# SparkFun_TMC6300_Breakout.net
KiCad netlist of a schematic drawn in EAGLE
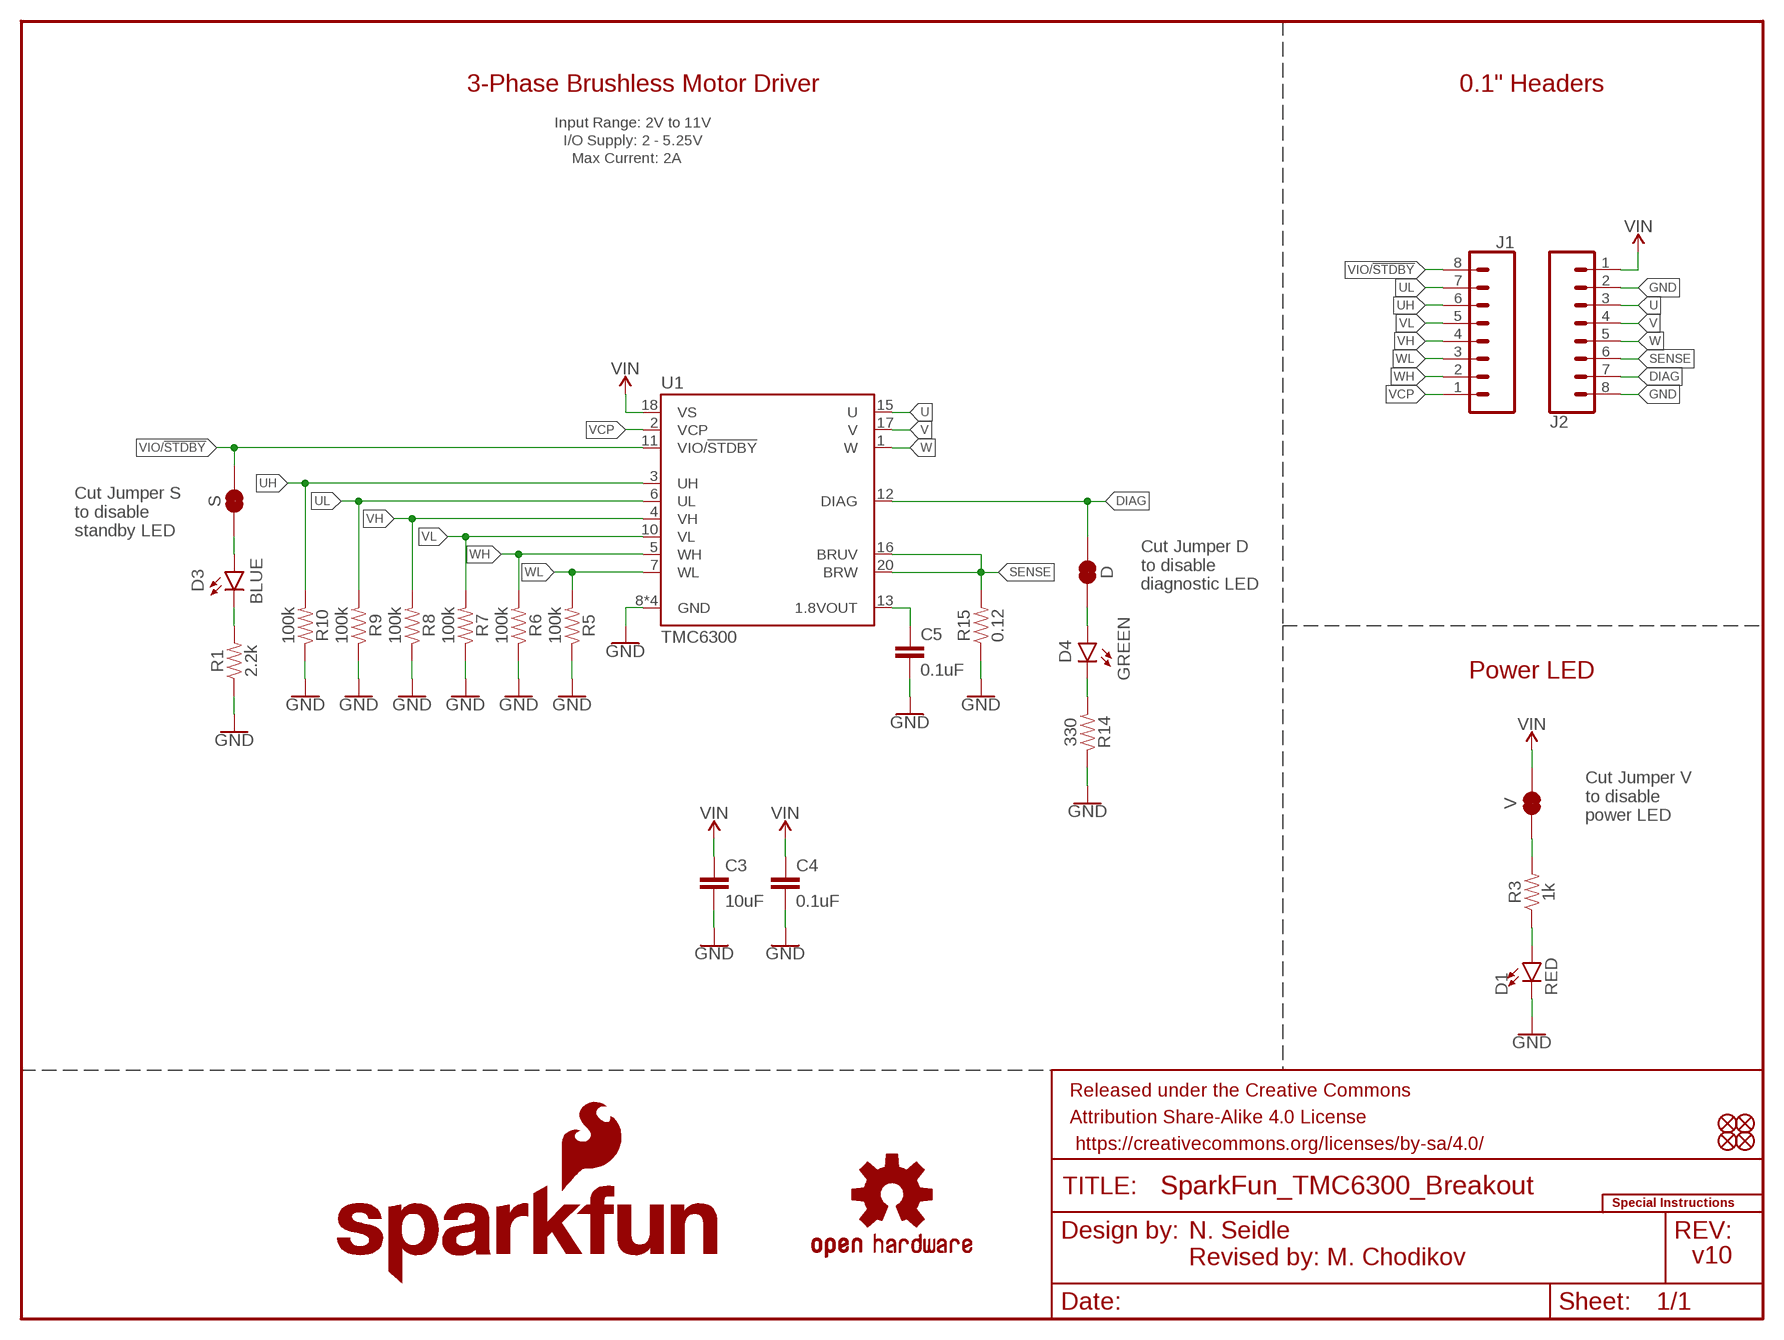
[diagram p0: schematic, sheet 1]

(export (version "E")
  (design (tool "Eeschema 10.0.6"))
  (components
    (comp (ref "C3")
      (value "10uF")
      (footprint "eagle-import:0805")
      (libsource (lib "eagle-import") (part "10UF-0805-25V-10%"))
    )
    (comp (ref "C4")
      (value "0.1uF")
      (footprint "eagle-import:0603")
      (libsource (lib "eagle-import") (part "0.1UF-0603-25V-10%-X7R-WE"))
    )
    (comp (ref "C5")
      (value "0.1uF")
      (footprint "eagle-import:0603")
      (libsource (lib "eagle-import") (part "0.1UF-0603-25V-10%-X7R-WE"))
    )
    (comp (ref "D")
      (value "JUMPER-SMT_2_NC_TRACE_SILK")
      (footprint "eagle-import:SMT-JUMPER_2_NC_TRACE_SILK")
      (libsource (lib "eagle-import") (part "JUMPER-SMT_2_NC_TRACE_SILK"))
    )
    (comp (ref "D1")
      (value "RED")
      (footprint "eagle-import:LED-0603")
      (libsource (lib "eagle-import") (part "LED-RED0603"))
    )
    (comp (ref "D3")
      (value "BLUE")
      (footprint "eagle-import:LED-0603")
      (libsource (lib "eagle-import") (part "LED-BLUE0603"))
    )
    (comp (ref "D4")
      (value "GREEN")
      (footprint "eagle-import:LED-0603")
      (libsource (lib "eagle-import") (part "LED-GREEN0603"))
    )
    (comp (ref "FD1")
      (value "FIDUCIALUFIDUCIAL")
      (footprint "eagle-import:FIDUCIAL-MICRO")
      (libsource (lib "eagle-import") (part "FIDUCIALUFIDUCIAL"))
    )
    (comp (ref "FD2")
      (value "FIDUCIALUFIDUCIAL")
      (footprint "eagle-import:FIDUCIAL-MICRO")
      (libsource (lib "eagle-import") (part "FIDUCIALUFIDUCIAL"))
    )
    (comp (ref "FD3")
      (value "FIDUCIALUFIDUCIAL")
      (footprint "eagle-import:FIDUCIAL-MICRO")
      (libsource (lib "eagle-import") (part "FIDUCIALUFIDUCIAL"))
    )
    (comp (ref "FD4")
      (value "FIDUCIALUFIDUCIAL")
      (footprint "eagle-import:FIDUCIAL-MICRO")
      (libsource (lib "eagle-import") (part "FIDUCIALUFIDUCIAL"))
    )
    (comp (ref "FRAME1")
      (value "FRAME-LETTER")
      (footprint "eagle-import:CREATIVE_COMMONS")
      (fields (field (name "DESIGNER") "Ricardo Ramos"))
      (libsource (lib "eagle-import") (part "FRAME-LETTER"))
    )
    (comp (ref "J1")
      (value "CONN_08LOCK_NO_SILK")
      (footprint "eagle-import:1X08_LOCK_NO_SILK")
      (libsource (lib "eagle-import") (part "CONN_08LOCK_NO_SILK"))
    )
    (comp (ref "J2")
      (value "CONN_08LOCK_NO_SILK")
      (footprint "eagle-import:1X08_LOCK_NO_SILK")
      (libsource (lib "eagle-import") (part "CONN_08LOCK_NO_SILK"))
    )
    (comp (ref "LOGO2")
      (value "SPECIAL_INSTRUCTIONS-ORDERING")
      (footprint "eagle-import:ORDERING_INSTRUCTIONS")
      (libsource (lib "eagle-import") (part "SPECIAL_INSTRUCTIONS-ORDERING"))
    )
    (comp (ref "LOGO3")
      (value "SFE_LOGO_NAME.08_INCH")
      (footprint "eagle-import:SFE_LOGO_NAME_.08")
      (libsource (lib "eagle-import") (part "SFE_LOGO_NAME.08_INCH"))
    )
    (comp (ref "LOGO4")
      (value "SFE_LOGO_FLAME.1_INCH")
      (footprint "eagle-import:SFE_LOGO_FLAME_.1")
      (libsource (lib "eagle-import") (part "SFE_LOGO_FLAME.1_INCH"))
    )
    (comp (ref "LOGO5")
      (value "OSHW-LOGOS")
      (footprint "eagle-import:OSHW-LOGO-S")
      (libsource (lib "eagle-import") (part "OSHW-LOGOS"))
    )
    (comp (ref "R1")
      (value "2.2k")
      (footprint "eagle-import:0603")
      (libsource (lib "eagle-import") (part "2.2KOHM-0603-1/10W-1%"))
    )
    (comp (ref "R3")
      (value "1k")
      (footprint "eagle-import:0603")
      (libsource (lib "eagle-import") (part "1KOHM-0603-1/10W-1%"))
    )
    (comp (ref "R5")
      (value "100k")
      (footprint "eagle-import:0603")
      (libsource (lib "eagle-import") (part "100KOHM-0603-1/10W-1%"))
    )
    (comp (ref "R6")
      (value "100k")
      (footprint "eagle-import:0603")
      (libsource (lib "eagle-import") (part "100KOHM-0603-1/10W-1%"))
    )
    (comp (ref "R7")
      (value "100k")
      (footprint "eagle-import:0603")
      (libsource (lib "eagle-import") (part "100KOHM-0603-1/10W-1%"))
    )
    (comp (ref "R8")
      (value "100k")
      (footprint "eagle-import:0603")
      (libsource (lib "eagle-import") (part "100KOHM-0603-1/10W-1%"))
    )
    (comp (ref "R9")
      (value "100k")
      (footprint "eagle-import:0603")
      (libsource (lib "eagle-import") (part "100KOHM-0603-1/10W-1%"))
    )
    (comp (ref "R10")
      (value "100k")
      (footprint "eagle-import:0603")
      (libsource (lib "eagle-import") (part "100KOHM-0603-1/10W-1%"))
    )
    (comp (ref "R14")
      (value "330")
      (footprint "eagle-import:0603")
      (libsource (lib "eagle-import") (part "330OHM-0603-1/10W-1%"))
    )
    (comp (ref "R15")
      (value "0.12")
      (footprint "eagle-import:1206")
      (libsource (lib "eagle-import") (part "0.12OHM-1206-1/2W-1%"))
    )
    (comp (ref "S")
      (value "JUMPER-SMT_2_NC_TRACE_SILK")
      (footprint "eagle-import:SMT-JUMPER_2_NC_TRACE_SILK")
      (libsource (lib "eagle-import") (part "JUMPER-SMT_2_NC_TRACE_SILK"))
    )
    (comp (ref "U1")
      (value "TMC6300")
      (footprint "eagle-import:QFN-20")
      (libsource (lib "eagle-import") (part "TMC6300"))
    )
    (comp (ref "V")
      (value "JUMPER-SMT_2_NC_TRACE_SILK")
      (footprint "eagle-import:SMT-JUMPER_2_NC_TRACE_SILK")
      (libsource (lib "eagle-import") (part "JUMPER-SMT_2_NC_TRACE_SILK"))
    )
  )
  (nets
    (net (code "1") (name "/VIO{slash}~{STDBY}") (class "Default")
      (node (ref "J1") (pin "8") (pinfunction "8_8") (pintype "passive"))
      (node (ref "S") (pin "2") (pinfunction "2_2") (pintype "passive"))
      (node (ref "U1") (pin "11") (pinfunction "VIO/~{STDBY}_11") (pintype "bidirectional"))
    )
    (net (code "2") (name "DIAG") (class "Default")
      (node (ref "D") (pin "2") (pinfunction "2_2") (pintype "passive"))
      (node (ref "J2") (pin "7") (pinfunction "7_7") (pintype "passive"))
      (node (ref "U1") (pin "12") (pinfunction "DIAG_12") (pintype "bidirectional"))
    )
    (net (code "3") (name "GND") (class "Default")
      (node (ref "C3") (pin "2") (pinfunction "2_2") (pintype "passive"))
      (node (ref "C4") (pin "2") (pinfunction "2_2") (pintype "passive"))
      (node (ref "C5") (pin "2") (pinfunction "2_2") (pintype "passive"))
      (node (ref "D1") (pin "C") (pinfunction "C_C") (pintype "passive"))
      (node (ref "J2") (pin "2") (pinfunction "2_2") (pintype "passive"))
      (node (ref "J2") (pin "8") (pinfunction "8_8") (pintype "passive"))
      (node (ref "R1") (pin "1") (pinfunction "1_1") (pintype "passive"))
      (node (ref "R10") (pin "1") (pinfunction "1_1") (pintype "passive"))
      (node (ref "R14") (pin "1") (pinfunction "1_1") (pintype "passive"))
      (node (ref "R15") (pin "1") (pinfunction "1_1") (pintype "passive"))
      (node (ref "R5") (pin "1") (pinfunction "1_1") (pintype "passive"))
      (node (ref "R6") (pin "1") (pinfunction "1_1") (pintype "passive"))
      (node (ref "R7") (pin "1") (pinfunction "1_1") (pintype "passive"))
      (node (ref "R8") (pin "1") (pinfunction "1_1") (pintype "passive"))
      (node (ref "R9") (pin "1") (pinfunction "1_1") (pintype "passive"))
      (node (ref "U1") (pin "14") (pinfunction "GND_14") (pintype "bidirectional"))
      (node (ref "U1") (pin "8") (pinfunction "GND_8") (pintype "bidirectional"))
      (node (ref "U1") (pin "9") (pinfunction "GND_9") (pintype "bidirectional"))
      (node (ref "U1") (pin "PAD") (pinfunction "GND_PAD") (pintype "bidirectional"))
    )
    (net (code "4") (name "Net-(D-Pad1)") (class "Default")
      (node (ref "D") (pin "1") (pinfunction "1_1") (pintype "passive"))
      (node (ref "D4") (pin "A") (pinfunction "A_A") (pintype "passive"))
    )
    (net (code "5") (name "Net-(D1-PadA)") (class "Default")
      (node (ref "D1") (pin "A") (pinfunction "A_A") (pintype "passive"))
      (node (ref "R3") (pin "1") (pinfunction "1_1") (pintype "passive"))
    )
    (net (code "6") (name "Net-(D3-PadA)") (class "Default")
      (node (ref "D3") (pin "A") (pinfunction "A_A") (pintype "passive"))
      (node (ref "S") (pin "1") (pinfunction "1_1") (pintype "passive"))
    )
    (net (code "7") (name "Net-(D3-PadC)") (class "Default")
      (node (ref "D3") (pin "C") (pinfunction "C_C") (pintype "passive"))
      (node (ref "R1") (pin "2") (pinfunction "2_2") (pintype "passive"))
    )
    (net (code "8") (name "Net-(D4-PadC)") (class "Default")
      (node (ref "D4") (pin "C") (pinfunction "C_C") (pintype "passive"))
      (node (ref "R14") (pin "2") (pinfunction "2_2") (pintype "passive"))
    )
    (net (code "9") (name "Net-(R3-Pad2)") (class "Default")
      (node (ref "R3") (pin "2") (pinfunction "2_2") (pintype "passive"))
      (node (ref "V") (pin "1") (pinfunction "1_1") (pintype "passive"))
    )
    (net (code "10") (name "Net-(U1-1.8VOUT)") (class "Default")
      (node (ref "C5") (pin "1") (pinfunction "1_1") (pintype "passive"))
      (node (ref "U1") (pin "13") (pinfunction "1.8VOUT_13") (pintype "bidirectional"))
    )
    (net (code "11") (name "SENSE") (class "Default")
      (node (ref "J2") (pin "6") (pinfunction "6_6") (pintype "passive"))
      (node (ref "R15") (pin "2") (pinfunction "2_2") (pintype "passive"))
      (node (ref "U1") (pin "16") (pinfunction "BRUV_16") (pintype "bidirectional"))
      (node (ref "U1") (pin "20") (pinfunction "BRW_20") (pintype "bidirectional"))
    )
    (net (code "12") (name "U") (class "Default")
      (node (ref "J2") (pin "3") (pinfunction "3_3") (pintype "passive"))
      (node (ref "U1") (pin "15") (pinfunction "U_15") (pintype "bidirectional"))
    )
    (net (code "13") (name "UH") (class "Default")
      (node (ref "J1") (pin "6") (pinfunction "6_6") (pintype "passive"))
      (node (ref "R10") (pin "2") (pinfunction "2_2") (pintype "passive"))
      (node (ref "U1") (pin "3") (pinfunction "UH_3") (pintype "bidirectional"))
    )
    (net (code "14") (name "UL") (class "Default")
      (node (ref "J1") (pin "7") (pinfunction "7_7") (pintype "passive"))
      (node (ref "R9") (pin "2") (pinfunction "2_2") (pintype "passive"))
      (node (ref "U1") (pin "6") (pinfunction "UL_6") (pintype "bidirectional"))
    )
    (net (code "15") (name "V") (class "Default")
      (node (ref "J2") (pin "4") (pinfunction "4_4") (pintype "passive"))
      (node (ref "U1") (pin "17") (pinfunction "V_17") (pintype "bidirectional"))
    )
    (net (code "16") (name "VCP") (class "Default")
      (node (ref "J1") (pin "1") (pinfunction "1_1") (pintype "passive"))
      (node (ref "U1") (pin "2") (pinfunction "VCP_2") (pintype "bidirectional"))
    )
    (net (code "17") (name "VH") (class "Default")
      (node (ref "J1") (pin "4") (pinfunction "4_4") (pintype "passive"))
      (node (ref "R8") (pin "2") (pinfunction "2_2") (pintype "passive"))
      (node (ref "U1") (pin "4") (pinfunction "VH_4") (pintype "bidirectional"))
    )
    (net (code "18") (name "VIN") (class "Default")
      (node (ref "C3") (pin "1") (pinfunction "1_1") (pintype "passive"))
      (node (ref "C4") (pin "1") (pinfunction "1_1") (pintype "passive"))
      (node (ref "J2") (pin "1") (pinfunction "1_1") (pintype "passive"))
      (node (ref "U1") (pin "18") (pinfunction "VS_18") (pintype "bidirectional"))
      (node (ref "V") (pin "2") (pinfunction "2_2") (pintype "passive"))
    )
    (net (code "19") (name "VL") (class "Default")
      (node (ref "J1") (pin "5") (pinfunction "5_5") (pintype "passive"))
      (node (ref "R7") (pin "2") (pinfunction "2_2") (pintype "passive"))
      (node (ref "U1") (pin "10") (pinfunction "VL_10") (pintype "bidirectional"))
    )
    (net (code "20") (name "W") (class "Default")
      (node (ref "J2") (pin "5") (pinfunction "5_5") (pintype "passive"))
      (node (ref "U1") (pin "1") (pinfunction "W_1") (pintype "bidirectional"))
    )
    (net (code "21") (name "WH") (class "Default")
      (node (ref "J1") (pin "2") (pinfunction "2_2") (pintype "passive"))
      (node (ref "R6") (pin "2") (pinfunction "2_2") (pintype "passive"))
      (node (ref "U1") (pin "5") (pinfunction "WH_5") (pintype "bidirectional"))
    )
    (net (code "22") (name "WL") (class "Default")
      (node (ref "J1") (pin "3") (pinfunction "3_3") (pintype "passive"))
      (node (ref "R5") (pin "2") (pinfunction "2_2") (pintype "passive"))
      (node (ref "U1") (pin "7") (pinfunction "WL_7") (pintype "bidirectional"))
    )
  )
)
